# ShutterController.net
KiCad netlist of a schematic drawn in EasyEDA
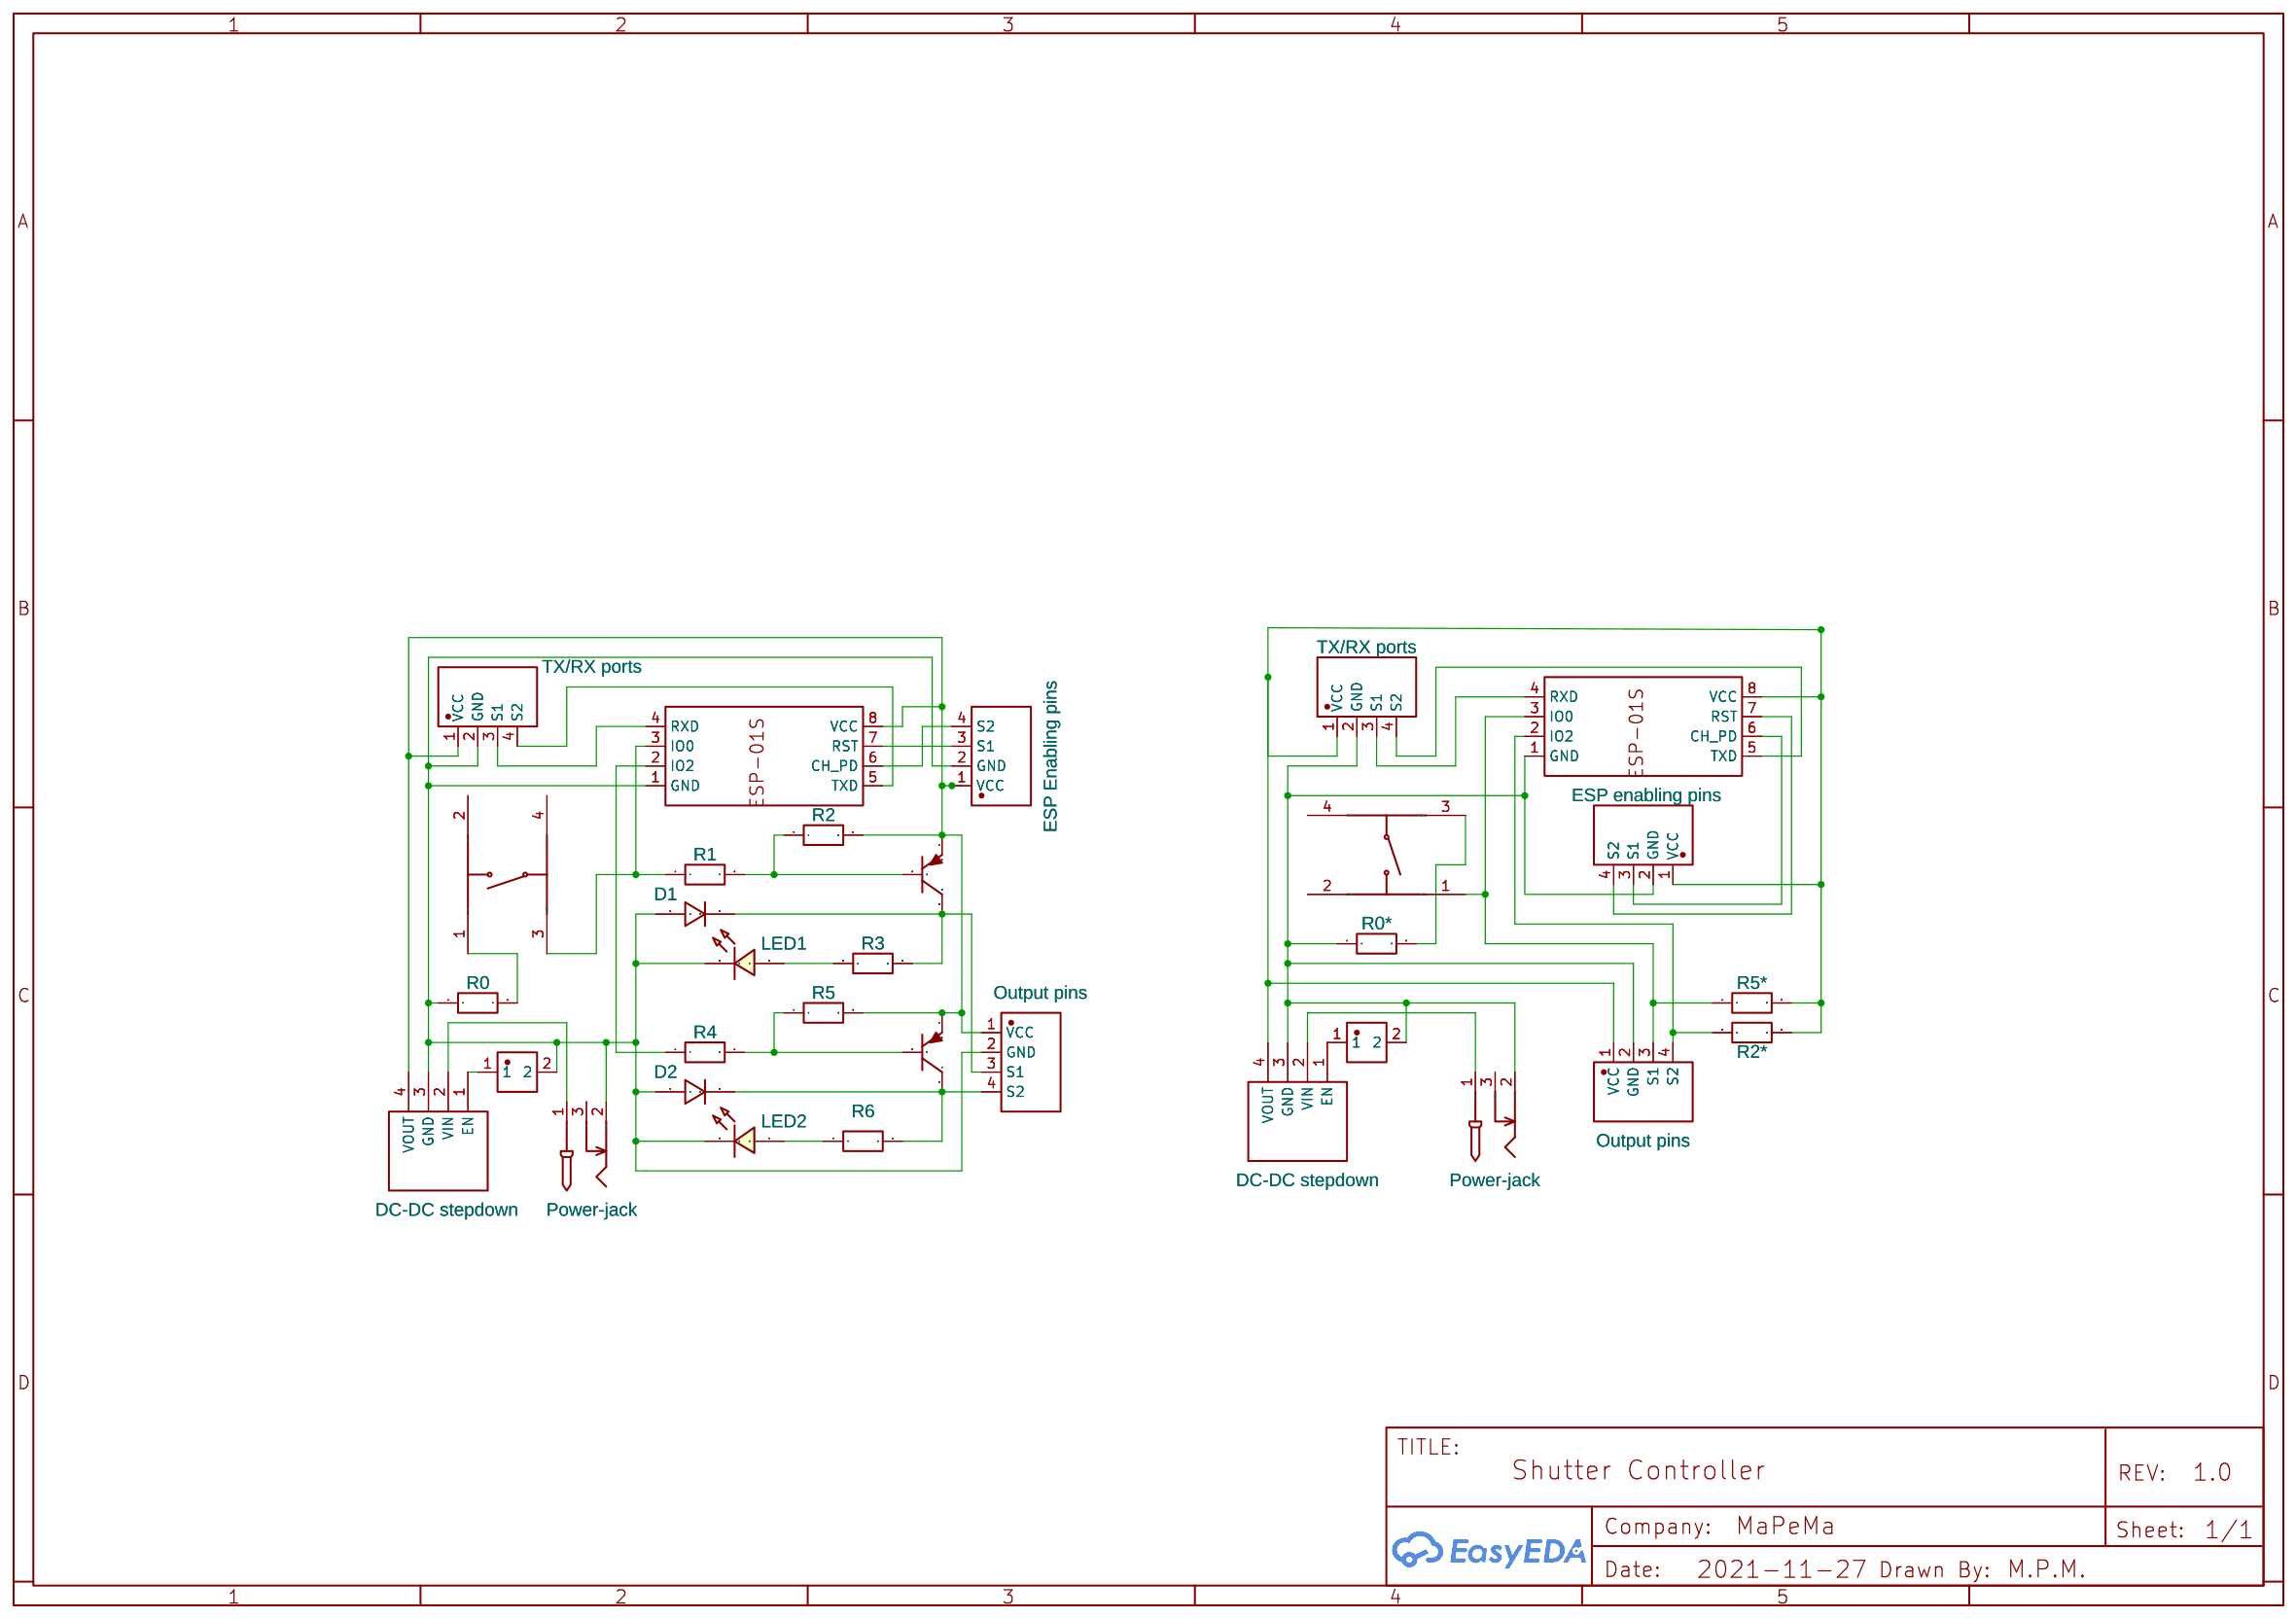
[diagram p0: schematic sheet]

(export (version "E")
  (design (tool "Eeschema 10.0.6"))
  (components
    (comp (ref "D1")
      (value "1N4007")
      (fields (field (name "BOM_Supplier Part") "C106903"))
      (libsource (lib "") (part "1N4007"))
    )
    (comp (ref "D2")
      (value "1N4007")
      (fields (field (name "BOM_Supplier Part") "C106903"))
      (libsource (lib "") (part "1N4007"))
    )
    (comp (ref "LED1")
      (value "LED-TH-3mm_R")
      (fields
        (field (name "BOM_Manufacturer Part") "204-10SDRD/S530-A3-L")
        (field (name "BOM_Supplier Part") "C84774")
      )
      (libsource (lib "") (part "LED-TH-3mm_R"))
    )
    (comp (ref "LED2")
      (value "LED-TH-3mm_R")
      (fields
        (field (name "BOM_Manufacturer Part") "204-10SDRD/S530-A3-L")
        (field (name "BOM_Supplier Part") "C84774")
      )
      (libsource (lib "") (part "LED-TH-3mm_R"))
    )
    (comp (ref "P1")
      (value "Power-jack")
      (fields (field (name "BOM_Manufacturer Part") "DC005-2.5MM"))
      (libsource (lib "") (part "DC005-2.5MM"))
    )
    (comp (ref "P2")
      (value "Power-jack")
      (fields (field (name "BOM_Manufacturer Part") "DC005-2.5MM"))
      (libsource (lib "") (part "DC005-2.5MM"))
    )
    (comp (ref "Q1") (value "Bipolar PNP-SIL 2.54mm") (libsource (lib "") (part "Bipolar PNP-SIL 2.54mm")))
    (comp (ref "Q3") (value "Bipolar PNP-SIL 2.54mm") (libsource (lib "") (part "Bipolar PNP-SIL 2.54mm")))
    (comp (ref "R0") (value "1k") (libsource (lib "") (part "R_AXIAL-0.3_EU")))
    (comp (ref "R0*") (value "1k") (libsource (lib "") (part "R_AXIAL-0.3_EU_3")))
    (comp (ref "R1") (value "1k") (libsource (lib "") (part "R_AXIAL-0.3_EU")))
    (comp (ref "R2") (value "10k") (libsource (lib "") (part "R_AXIAL-0.3_EU")))
    (comp (ref "R2*") (value "1k") (libsource (lib "") (part "R_AXIAL-0.3_EU_2")))
    (comp (ref "R3") (value "1k") (libsource (lib "") (part "R_AXIAL-0.3_EU")))
    (comp (ref "R4") (value "1k") (libsource (lib "") (part "R_AXIAL-0.3_EU")))
    (comp (ref "R5") (value "10k") (libsource (lib "") (part "R_AXIAL-0.3_EU")))
    (comp (ref "R5*") (value "1k") (libsource (lib "") (part "R_AXIAL-0.3_EU_1")))
    (comp (ref "R6") (value "1k") (libsource (lib "") (part "R_AXIAL-0.3_EU")))
    (comp (ref "SW1")
      (value "Tactile_Switch_12*12*7.3 4 3 2 1")
      (fields (field (name "BOM_Manufacturer Part") "TACTS-24N-F / TACTS-24K-F // B3F-40xx / B3F-50xx"))
      (libsource (lib "") (part "Tactile_Switch_12*12*7.3 4 3 2 1"))
    )
    (comp (ref "SW2")
      (value "Tactile_Switch_12*12*7.3 4 3 2 1")
      (fields (field (name "BOM_Manufacturer Part") "TACTS-24N-F / TACTS-24K-F // B3F-40xx / B3F-50xx"))
      (libsource (lib "") (part "Tactile_Switch_12*12*7.3 4 3 2 1_1"))
    )
    (comp (ref "U1")
      (value "DC-DC stepdown")
      (fields (field (name "BOM_Manufacturer Part") "HW-613") (field (name "BOM_Supplier Part") "100.387.25"))
      (libsource (lib "") (part "STDN-3A24-ADJ"))
    )
    (comp (ref "U2")
      (value "ESP-01S")
      (fields (field (name "BOM_Supplier Part") "C111009"))
      (libsource (lib "") (part "ESP-01S_1"))
    )
    (comp (ref "U3") (value "TX/RX ports") (libsource (lib "") (part "Simple 4pin connector")))
    (comp (ref "U4") (value "Output pins") (libsource (lib "") (part "Simple 4pin connector_3")))
    (comp (ref "U5") (value "TX/RX ports") (libsource (lib "") (part "Simple 4pin connector")))
    (comp (ref "U6") (value "Simple 2pin connector") (libsource (lib "") (part "Simple 2pin connector")))
    (comp (ref "U7") (value "ESP Enabling pins") (libsource (lib "") (part "Simple 4pin connector_2")))
    (comp (ref "U8")
      (value "DC-DC stepdown")
      (fields (field (name "BOM_Manufacturer Part") "HW-613") (field (name "BOM_Supplier Part") "100.387.25"))
      (libsource (lib "") (part "STDN-3A24-ADJ"))
    )
    (comp (ref "U9")
      (value "ESP-01S")
      (fields (field (name "BOM_Supplier Part") "C111009"))
      (libsource (lib "") (part "ESP-01S"))
    )
    (comp (ref "U10") (value "ESP enabling pins") (libsource (lib "") (part "Simple 4pin connector_4")))
    (comp (ref "U11") (value "Output pins") (libsource (lib "") (part "Simple 4pin connector_1")))
    (comp (ref "U12") (value "Simple 2pin connector") (libsource (lib "") (part "Simple 2pin connector")))
  )
  (nets
    (net (code "1") (name "Net-(LED1-Pad1)") (class "Default")
      (node (ref "LED1") (pin "1") (pinfunction "1_1") (pintype "unspecified"))
      (node (ref "R3") (pin "1") (pinfunction "1_1") (pintype "unspecified"))
    )
    (net (code "2") (name "Net-(LED2-Pad1)") (class "Default")
      (node (ref "LED2") (pin "1") (pinfunction "1_1") (pintype "unspecified"))
      (node (ref "R6") (pin "1") (pinfunction "1_1") (pintype "unspecified"))
    )
    (net (code "3") (name "Net-(Q1-B)") (class "Default")
      (node (ref "Q1") (pin "2") (pinfunction "B_2") (pintype "unspecified"))
      (node (ref "R1") (pin "2") (pinfunction "2_2") (pintype "unspecified"))
      (node (ref "R2") (pin "1") (pinfunction "1_1") (pintype "unspecified"))
    )
    (net (code "4") (name "Net-(Q1-C)") (class "Default")
      (node (ref "D1") (pin "1") (pinfunction "1_1") (pintype "unspecified"))
      (node (ref "Q1") (pin "3") (pinfunction "C_3") (pintype "unspecified"))
      (node (ref "R3") (pin "2") (pinfunction "2_2") (pintype "unspecified"))
      (node (ref "U4") (pin "3") (pinfunction "S1_3") (pintype "unspecified"))
    )
    (net (code "5") (name "Net-(Q1-E)") (class "Default")
      (node (ref "Q1") (pin "1") (pinfunction "E_1") (pintype "unspecified"))
      (node (ref "Q3") (pin "1") (pinfunction "E_1") (pintype "unspecified"))
      (node (ref "R2") (pin "2") (pinfunction "2_2") (pintype "unspecified"))
      (node (ref "R5") (pin "2") (pinfunction "2_2") (pintype "unspecified"))
      (node (ref "U1") (pin "4") (pinfunction "VOUT_4") (pintype "unspecified"))
      (node (ref "U2") (pin "8") (pinfunction "VCC_8") (pintype "unspecified"))
      (node (ref "U3") (pin "1") (pinfunction "VCC_1") (pintype "unspecified"))
      (node (ref "U4") (pin "1") (pinfunction "VCC_1") (pintype "unspecified"))
      (node (ref "U7") (pin "1") (pinfunction "VCC_1") (pintype "unspecified"))
    )
    (net (code "6") (name "Net-(Q3-B)") (class "Default")
      (node (ref "Q3") (pin "2") (pinfunction "B_2") (pintype "unspecified"))
      (node (ref "R4") (pin "2") (pinfunction "2_2") (pintype "unspecified"))
      (node (ref "R5") (pin "1") (pinfunction "1_1") (pintype "unspecified"))
    )
    (net (code "7") (name "Net-(Q3-C)") (class "Default")
      (node (ref "D2") (pin "1") (pinfunction "1_1") (pintype "unspecified"))
      (node (ref "Q3") (pin "3") (pinfunction "C_3") (pintype "unspecified"))
      (node (ref "R6") (pin "2") (pinfunction "2_2") (pintype "unspecified"))
      (node (ref "U4") (pin "4") (pinfunction "S2_4") (pintype "unspecified"))
    )
    (net (code "8") (name "Net-(SW1-B)") (class "Default")
      (node (ref "R0*") (pin "2") (pinfunction "2_2") (pintype "unspecified"))
      (node (ref "SW1") (pin "3") (pinfunction "B_3") (pintype "unspecified"))
    )
    (net (code "9") (name "Net-(SW1-D)") (class "Default")
      (node (ref "R2*") (pin "1") (pinfunction "1_1") (pintype "unspecified"))
      (node (ref "SW1") (pin "1") (pinfunction "D_1") (pintype "unspecified"))
      (node (ref "U11") (pin "3") (pinfunction "S1_3") (pintype "unspecified"))
      (node (ref "U9") (pin "3") (pinfunction "IO0_3") (pintype "unspecified"))
    )
    (net (code "10") (name "Net-(SW2-B)") (class "Default")
      (node (ref "R1") (pin "1") (pinfunction "1_1") (pintype "unspecified"))
      (node (ref "SW2") (pin "3") (pinfunction "B_3") (pintype "unspecified"))
      (node (ref "U2") (pin "3") (pinfunction "IO0_3") (pintype "unspecified"))
    )
    (net (code "11") (name "Net-(SW2-D)") (class "Default")
      (node (ref "R0") (pin "2") (pinfunction "2_2") (pintype "unspecified"))
      (node (ref "SW2") (pin "1") (pinfunction "D_1") (pintype "unspecified"))
    )
    (net (code "12") (name "Net-(U1-EN)") (class "Default")
      (node (ref "U1") (pin "1") (pinfunction "EN_1") (pintype "unspecified"))
      (node (ref "U6") (pin "1") (pinfunction "1_1") (pintype "unspecified"))
    )
    (net (code "13") (name "Net-(U1-GND)") (class "Default")
      (node (ref "D1") (pin "2") (pinfunction "2_2") (pintype "unspecified"))
      (node (ref "D2") (pin "2") (pinfunction "2_2") (pintype "unspecified"))
      (node (ref "LED1") (pin "2") (pinfunction "2_2") (pintype "unspecified"))
      (node (ref "LED2") (pin "2") (pinfunction "2_2") (pintype "unspecified"))
      (node (ref "P1") (pin "2") (pinfunction "2_2") (pintype "unspecified"))
      (node (ref "R0") (pin "1") (pinfunction "1_1") (pintype "unspecified"))
      (node (ref "U1") (pin "3") (pinfunction "GND_3") (pintype "unspecified"))
      (node (ref "U2") (pin "1") (pinfunction "GND_1") (pintype "unspecified"))
      (node (ref "U3") (pin "2") (pinfunction "GND_2") (pintype "unspecified"))
      (node (ref "U4") (pin "2") (pinfunction "GND_2") (pintype "unspecified"))
      (node (ref "U6") (pin "2") (pinfunction "2_2") (pintype "unspecified"))
      (node (ref "U7") (pin "2") (pinfunction "GND_2") (pintype "unspecified"))
    )
    (net (code "14") (name "Net-(U1-VIN)") (class "Default")
      (node (ref "P1") (pin "1") (pinfunction "1_1") (pintype "unspecified"))
      (node (ref "U1") (pin "2") (pinfunction "VIN_2") (pintype "unspecified"))
    )
    (net (code "15") (name "Net-(U2-CH_PD)") (class "Default")
      (node (ref "U2") (pin "6") (pinfunction "CH_PD_6") (pintype "unspecified"))
      (node (ref "U7") (pin "4") (pinfunction "S2_4") (pintype "unspecified"))
    )
    (net (code "16") (name "Net-(U2-IO2)") (class "Default")
      (node (ref "R4") (pin "1") (pinfunction "1_1") (pintype "unspecified"))
      (node (ref "U2") (pin "2") (pinfunction "IO2_2") (pintype "unspecified"))
    )
    (net (code "17") (name "Net-(U2-RST)") (class "Default")
      (node (ref "U2") (pin "7") (pinfunction "RST_7") (pintype "unspecified"))
      (node (ref "U7") (pin "3") (pinfunction "S1_3") (pintype "unspecified"))
    )
    (net (code "18") (name "Net-(U2-RXD)") (class "Default")
      (node (ref "U2") (pin "4") (pinfunction "RXD_4") (pintype "unspecified"))
      (node (ref "U3") (pin "3") (pinfunction "S1_3") (pintype "unspecified"))
    )
    (net (code "19") (name "Net-(U2-TXD)") (class "Default")
      (node (ref "U2") (pin "5") (pinfunction "TXD_5") (pintype "unspecified"))
      (node (ref "U3") (pin "4") (pinfunction "S2_4") (pintype "unspecified"))
    )
    (net (code "20") (name "Net-(U5-S1)") (class "Default")
      (node (ref "U5") (pin "3") (pinfunction "S1_3") (pintype "unspecified"))
      (node (ref "U9") (pin "4") (pinfunction "RXD_4") (pintype "unspecified"))
    )
    (net (code "21") (name "Net-(U5-S2)") (class "Default")
      (node (ref "U5") (pin "4") (pinfunction "S2_4") (pintype "unspecified"))
      (node (ref "U9") (pin "5") (pinfunction "TXD_5") (pintype "unspecified"))
    )
    (net (code "22") (name "Net-(U8-EN)") (class "Default")
      (node (ref "U12") (pin "1") (pinfunction "1_1") (pintype "unspecified"))
      (node (ref "U8") (pin "1") (pinfunction "EN_1") (pintype "unspecified"))
    )
    (net (code "23") (name "Net-(U8-VIN)") (class "Default")
      (node (ref "P2") (pin "1") (pinfunction "1_1") (pintype "unspecified"))
      (node (ref "U8") (pin "2") (pinfunction "VIN_2") (pintype "unspecified"))
    )
    (net (code "24") (name "Net-(U10-GND)") (class "Default")
      (node (ref "P2") (pin "2") (pinfunction "2_2") (pintype "unspecified"))
      (node (ref "R0*") (pin "1") (pinfunction "1_1") (pintype "unspecified"))
      (node (ref "U10") (pin "2") (pinfunction "GND_2") (pintype "unspecified"))
      (node (ref "U11") (pin "2") (pinfunction "GND_2") (pintype "unspecified"))
      (node (ref "U12") (pin "2") (pinfunction "2_2") (pintype "unspecified"))
      (node (ref "U5") (pin "2") (pinfunction "GND_2") (pintype "unspecified"))
      (node (ref "U8") (pin "3") (pinfunction "GND_3") (pintype "unspecified"))
      (node (ref "U9") (pin "1") (pinfunction "GND_1") (pintype "unspecified"))
    )
    (net (code "25") (name "Net-(U10-S1)") (class "Default")
      (node (ref "U10") (pin "3") (pinfunction "S1_3") (pintype "unspecified"))
      (node (ref "U9") (pin "6") (pinfunction "CH_PD_6") (pintype "unspecified"))
    )
    (net (code "26") (name "Net-(U10-S2)") (class "Default")
      (node (ref "U10") (pin "4") (pinfunction "S2_4") (pintype "unspecified"))
      (node (ref "U9") (pin "7") (pinfunction "RST_7") (pintype "unspecified"))
    )
    (net (code "27") (name "Net-(U10-VCC)") (class "Default")
      (node (ref "R2*") (pin "2") (pinfunction "2_2") (pintype "unspecified"))
      (node (ref "R5*") (pin "2") (pinfunction "2_2") (pintype "unspecified"))
      (node (ref "U10") (pin "1") (pinfunction "VCC_1") (pintype "unspecified"))
      (node (ref "U11") (pin "1") (pinfunction "VCC_1") (pintype "unspecified"))
      (node (ref "U5") (pin "1") (pinfunction "VCC_1") (pintype "unspecified"))
      (node (ref "U8") (pin "4") (pinfunction "VOUT_4") (pintype "unspecified"))
      (node (ref "U9") (pin "8") (pinfunction "VCC_8") (pintype "unspecified"))
    )
    (net (code "28") (name "Net-(U11-S2)") (class "Default")
      (node (ref "R5*") (pin "1") (pinfunction "1_1") (pintype "unspecified"))
      (node (ref "U11") (pin "4") (pinfunction "S2_4") (pintype "unspecified"))
      (node (ref "U9") (pin "2") (pinfunction "IO2_2") (pintype "unspecified"))
    )
    (net (code "29") (name "unconnected-(P1-Pad3)") (class "Default")
      (node (ref "P1") (pin "3") (pinfunction "3_3") (pintype "unspecified"))
    )
    (net (code "30") (name "unconnected-(P2-Pad3)") (class "Default")
      (node (ref "P2") (pin "3") (pinfunction "3_3") (pintype "unspecified"))
    )
    (net (code "31") (name "unconnected-(SW1-A-Pad4)") (class "Default")
      (node (ref "SW1") (pin "4") (pinfunction "A_4") (pintype "unspecified"))
    )
    (net (code "32") (name "unconnected-(SW1-C-Pad2)") (class "Default")
      (node (ref "SW1") (pin "2") (pinfunction "C_2") (pintype "unspecified"))
    )
    (net (code "33") (name "unconnected-(SW2-A-Pad4)") (class "Default")
      (node (ref "SW2") (pin "4") (pinfunction "A_4") (pintype "unspecified"))
    )
    (net (code "34") (name "unconnected-(SW2-C-Pad2)") (class "Default")
      (node (ref "SW2") (pin "2") (pinfunction "C_2") (pintype "unspecified"))
    )
  )
)
